# Adafruit_LIS3MDL_LSM6DSOX.net
KiCad netlist of a schematic drawn in EAGLE
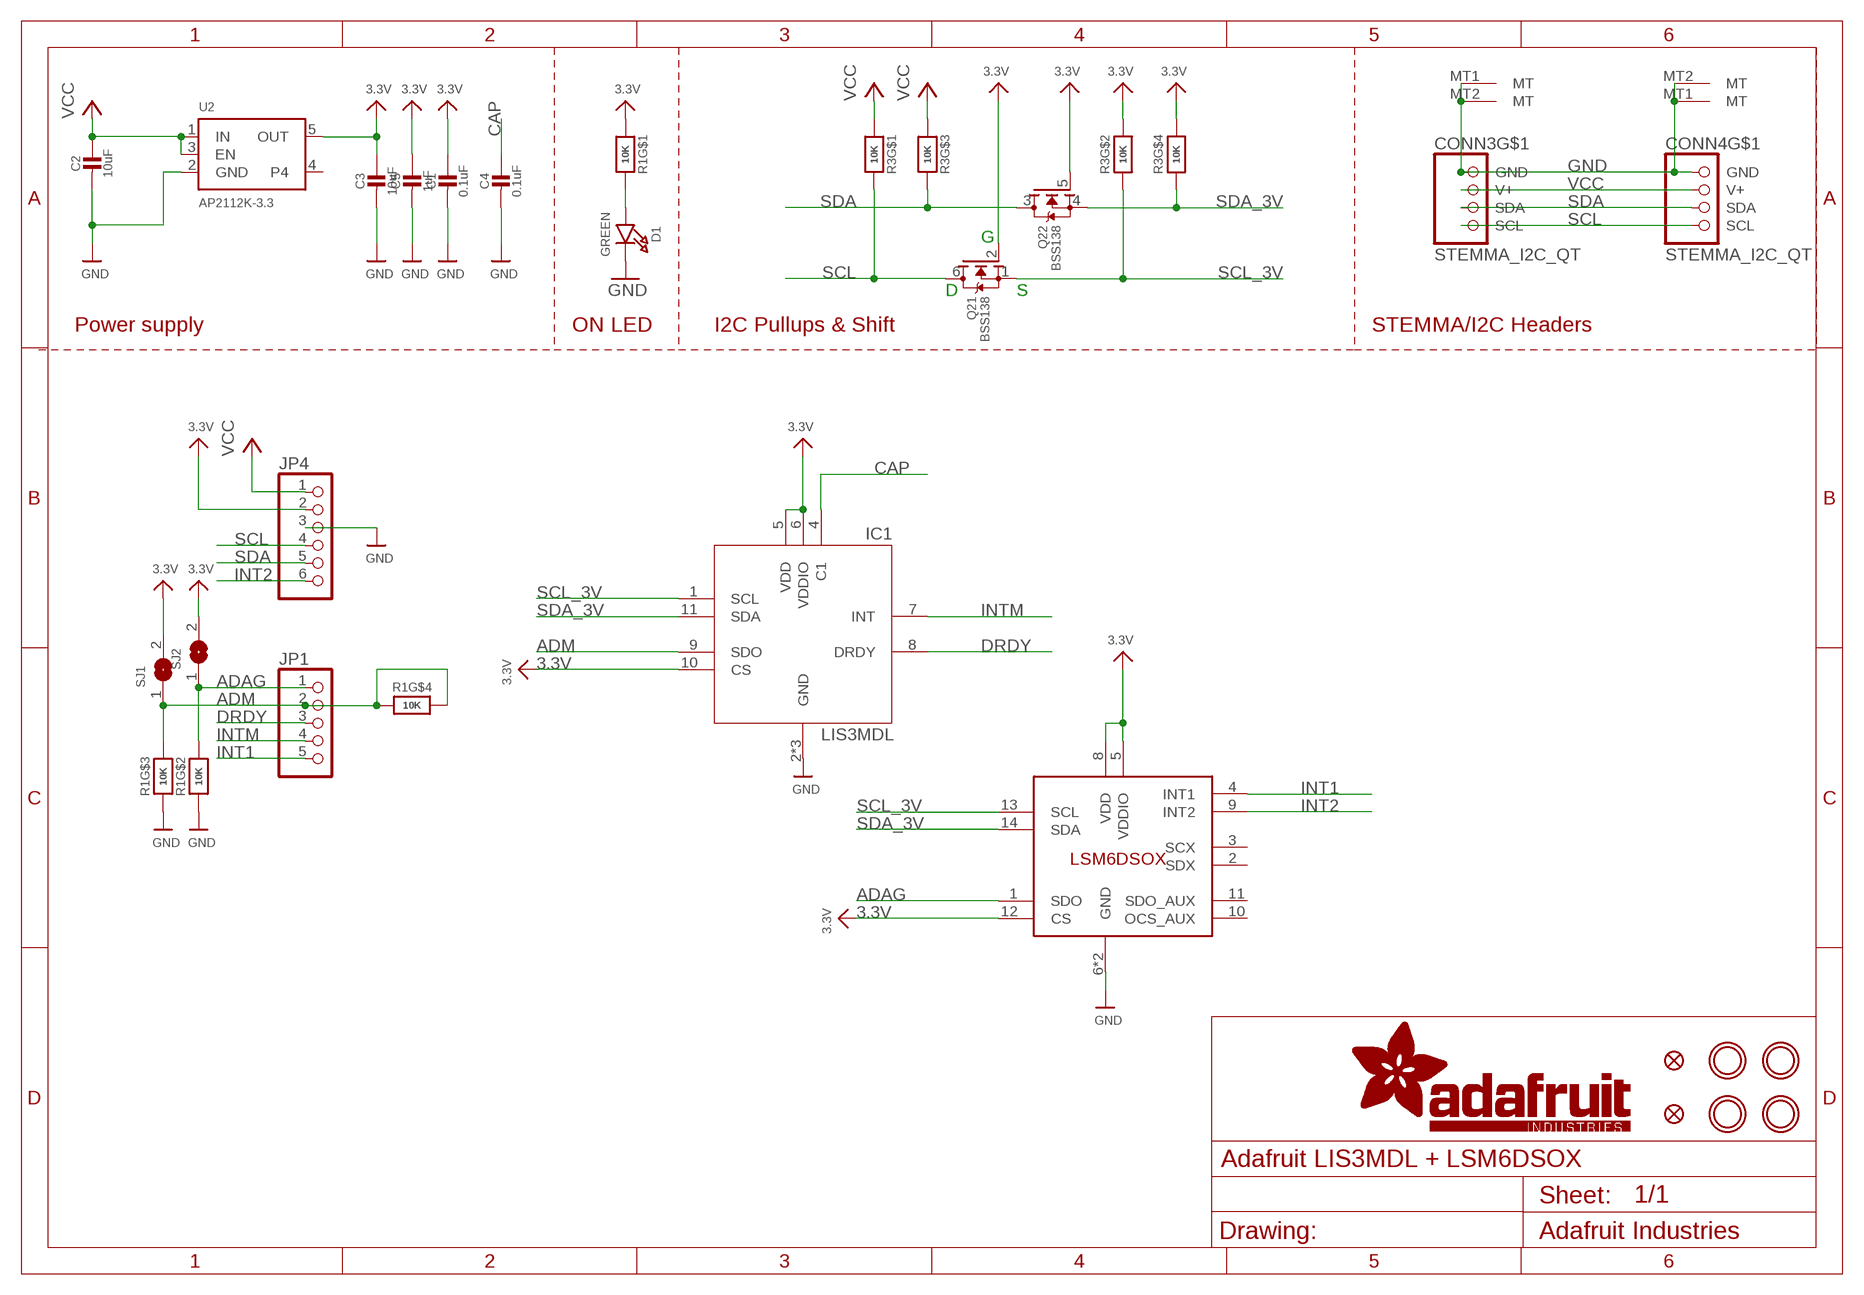
[diagram p0: schematic, sheet 1]

(export (version "E")
  (design (tool "Eeschema 10.0.6"))
  (components
    (comp (ref "C1")
      (value "0.1uF")
      (footprint "eagle-import:0603-NO")
      (libsource (lib "eagle-import") (part "CAP_CERAMIC0603_NO"))
    )
    (comp (ref "C2")
      (value "10uF")
      (footprint "eagle-import:0805-NO")
      (libsource (lib "eagle-import") (part "CAP_CERAMIC0805-NOOUTLINE"))
    )
    (comp (ref "C3")
      (value "10uF")
      (footprint "eagle-import:0805-NO")
      (libsource (lib "eagle-import") (part "CAP_CERAMIC0805-NOOUTLINE"))
    )
    (comp (ref "C4")
      (value "0.1uF")
      (footprint "eagle-import:0603-NO")
      (libsource (lib "eagle-import") (part "CAP_CERAMIC0603_NO"))
    )
    (comp (ref "C5")
      (value "1uF")
      (footprint "eagle-import:0603-NO")
      (libsource (lib "eagle-import") (part "CAP_CERAMIC0603_NO"))
    )
    (comp (ref "CONN3")
      (value "STEMMA_I2C_QT")
      (footprint "eagle-import:JST_SH4")
      (libsource (lib "eagle-import") (part "STEMMA_I2C_QT"))
    )
    (comp (ref "CONN4")
      (value "STEMMA_I2C_QT")
      (footprint "eagle-import:JST_SH4")
      (libsource (lib "eagle-import") (part "STEMMA_I2C_QT"))
    )
    (comp (ref "D1")
      (value "GREEN")
      (footprint "eagle-import:CHIPLED_0603_NOOUTLINE")
      (libsource (lib "eagle-import") (part "LED0603_NOOUTLINE"))
    )
    (comp (ref "FID3")
      (value "FIDUCIAL_1MM")
      (footprint "eagle-import:FIDUCIAL_1MM")
      (libsource (lib "eagle-import") (part "FIDUCIAL_1MM"))
    )
    (comp (ref "FID4")
      (value "FIDUCIAL_1MM")
      (footprint "eagle-import:FIDUCIAL_1MM")
      (libsource (lib "eagle-import") (part "FIDUCIAL_1MM"))
    )
    (comp (ref "IC1")
      (value "LIS3MDL")
      (footprint "eagle-import:LGA12_2X2MM")
      (libsource (lib "eagle-import") (part "LIS3MDL"))
    )
    (comp (ref "JP1")
      (value "HEADER-1X570MIL")
      (footprint "eagle-import:1X05_ROUND_70")
      (libsource (lib "eagle-import") (part "HEADER-1X570MIL"))
    )
    (comp (ref "JP4")
      (value "HEADER-1X670MIL")
      (footprint "eagle-import:1X06_ROUND_70")
      (libsource (lib "eagle-import") (part "HEADER-1X670MIL"))
    )
    (comp (ref "Q2")
      (value "BSS138")
      (footprint "eagle-import:SOT363")
      (libsource (lib "eagle-import") (part "MOSFET-N_DUAL"))
    )
    (comp (ref "R1")
      (value "10K")
      (footprint "eagle-import:RESPACK_4X0603")
      (libsource (lib "eagle-import") (part "RESISTOR_4PACK"))
    )
    (comp (ref "R3")
      (value "10K")
      (footprint "eagle-import:RESPACK_4X0603")
      (libsource (lib "eagle-import") (part "RESISTOR_4PACK"))
    )
    (comp (ref "SJ1")
      (value "SOLDERJUMPER")
      (footprint "eagle-import:SOLDERJUMPER_ARROW_NOPASTE")
      (libsource (lib "eagle-import") (part "SOLDERJUMPER"))
    )
    (comp (ref "SJ2")
      (value "SOLDERJUMPER")
      (footprint "eagle-import:SOLDERJUMPER_ARROW_NOPASTE")
      (libsource (lib "eagle-import") (part "SOLDERJUMPER"))
    )
    (comp (ref "U$1")
      (value "MOUNTINGHOLE2.5")
      (footprint "eagle-import:MOUNTINGHOLE_2.5_PLATED")
      (libsource (lib "eagle-import") (part "MOUNTINGHOLE2.5"))
    )
    (comp (ref "U$17")
      (value "MOUNTINGHOLE2.5")
      (footprint "eagle-import:MOUNTINGHOLE_2.5_PLATED")
      (libsource (lib "eagle-import") (part "MOUNTINGHOLE2.5"))
    )
    (comp (ref "U$19")
      (value "MOUNTINGHOLE2.5")
      (footprint "eagle-import:MOUNTINGHOLE_2.5_PLATED")
      (libsource (lib "eagle-import") (part "MOUNTINGHOLE2.5"))
    )
    (comp (ref "U$21")
      (value "MOUNTINGHOLE2.5")
      (footprint "eagle-import:MOUNTINGHOLE_2.5_PLATED")
      (libsource (lib "eagle-import") (part "MOUNTINGHOLE2.5"))
    )
    (comp (ref "U$35")
      (value "LSM6DSOX")
      (footprint "eagle-import:LGA-14L")
      (libsource (lib "eagle-import") (part "LSM6DSOX"))
    )
    (comp (ref "U2")
      (value "AP2112K-3.3")
      (footprint "eagle-import:SOT23-5")
      (libsource (lib "eagle-import") (part "VREG_SOT23-5"))
    )
  )
  (nets
    (net (code "1") (name "/ADAG") (class "Default")
      (node (ref "JP1") (pin "1") (pinfunction "1_1") (pintype "passive"))
      (node (ref "R1") (pin "7") (pinfunction "2_7") (pintype "passive"))
      (node (ref "SJ2") (pin "1") (pinfunction "1_1") (pintype "passive"))
      (node (ref "U$35") (pin "1") (pinfunction "SDO_1") (pintype "bidirectional"))
    )
    (net (code "2") (name "/ADM") (class "Default")
      (node (ref "IC1") (pin "9") (pinfunction "SDO_9") (pintype "bidirectional"))
      (node (ref "JP1") (pin "2") (pinfunction "2_2") (pintype "passive"))
      (node (ref "R1") (pin "4") (pinfunction "1_4") (pintype "passive"))
      (node (ref "R1") (pin "5") (pinfunction "2_5") (pintype "passive"))
      (node (ref "R1") (pin "6") (pinfunction "2_6") (pintype "passive"))
      (node (ref "SJ1") (pin "1") (pinfunction "1_1") (pintype "passive"))
    )
    (net (code "3") (name "/CAP") (class "Default")
      (node (ref "C4") (pin "1") (pinfunction "1_1") (pintype "passive"))
      (node (ref "IC1") (pin "4") (pinfunction "C1_4") (pintype "input"))
    )
    (net (code "4") (name "/DRDY") (class "Default")
      (node (ref "IC1") (pin "8") (pinfunction "DRDY_8") (pintype "output"))
      (node (ref "JP1") (pin "3") (pinfunction "3_3") (pintype "passive"))
    )
    (net (code "5") (name "/INT1") (class "Default")
      (node (ref "JP1") (pin "5") (pinfunction "5_5") (pintype "passive"))
      (node (ref "U$35") (pin "4") (pinfunction "INT1_4") (pintype "bidirectional"))
    )
    (net (code "6") (name "/INT2") (class "Default")
      (node (ref "JP4") (pin "6") (pinfunction "6_6") (pintype "passive"))
      (node (ref "U$35") (pin "9") (pinfunction "INT2_9") (pintype "bidirectional"))
    )
    (net (code "7") (name "/INTM") (class "Default")
      (node (ref "IC1") (pin "7") (pinfunction "INT_7") (pintype "output"))
      (node (ref "JP1") (pin "4") (pinfunction "4_4") (pintype "passive"))
    )
    (net (code "8") (name "/SCL") (class "Default")
      (node (ref "CONN3") (pin "4") (pinfunction "SCL_4") (pintype "passive"))
      (node (ref "CONN4") (pin "4") (pinfunction "SCL_4") (pintype "passive"))
      (node (ref "JP4") (pin "4") (pinfunction "4_4") (pintype "passive"))
      (node (ref "Q2") (pin "6") (pinfunction "D_6") (pintype "bidirectional"))
      (node (ref "R3") (pin "8") (pinfunction "2_8") (pintype "passive"))
    )
    (net (code "9") (name "/SCL_3V") (class "Default")
      (node (ref "IC1") (pin "1") (pinfunction "SCL_1") (pintype "input"))
      (node (ref "Q2") (pin "1") (pinfunction "S_1") (pintype "bidirectional"))
      (node (ref "R3") (pin "7") (pinfunction "2_7") (pintype "passive"))
      (node (ref "U$35") (pin "13") (pinfunction "SCL_13") (pintype "bidirectional"))
    )
    (net (code "10") (name "/SDA") (class "Default")
      (node (ref "CONN3") (pin "3") (pinfunction "SDA_3") (pintype "passive"))
      (node (ref "CONN4") (pin "3") (pinfunction "SDA_3") (pintype "passive"))
      (node (ref "JP4") (pin "5") (pinfunction "5_5") (pintype "passive"))
      (node (ref "Q2") (pin "3") (pinfunction "D_3") (pintype "bidirectional"))
      (node (ref "R3") (pin "6") (pinfunction "2_6") (pintype "passive"))
    )
    (net (code "11") (name "/SDA_3V") (class "Default")
      (node (ref "IC1") (pin "11") (pinfunction "SDA_11") (pintype "bidirectional"))
      (node (ref "Q2") (pin "4") (pinfunction "S_4") (pintype "bidirectional"))
      (node (ref "R3") (pin "5") (pinfunction "2_5") (pintype "passive"))
      (node (ref "U$35") (pin "14") (pinfunction "SDA_14") (pintype "bidirectional"))
    )
    (net (code "12") (name "3.3V") (class "Default")
      (node (ref "C1") (pin "1") (pinfunction "1_1") (pintype "passive"))
      (node (ref "C3") (pin "1") (pinfunction "1_1") (pintype "passive"))
      (node (ref "C5") (pin "1") (pinfunction "1_1") (pintype "passive"))
      (node (ref "IC1") (pin "10") (pinfunction "CS_10") (pintype "input"))
      (node (ref "IC1") (pin "5") (pinfunction "VDD_5") (pintype "power_in"))
      (node (ref "IC1") (pin "6") (pinfunction "VDDIO_6") (pintype "power_in"))
      (node (ref "JP4") (pin "2") (pinfunction "2_2") (pintype "passive"))
      (node (ref "Q2") (pin "2") (pinfunction "G_2") (pintype "bidirectional"))
      (node (ref "Q2") (pin "5") (pinfunction "G_5") (pintype "bidirectional"))
      (node (ref "R1") (pin "1") (pinfunction "1_1") (pintype "passive"))
      (node (ref "R3") (pin "2") (pinfunction "1_2") (pintype "passive"))
      (node (ref "R3") (pin "4") (pinfunction "1_4") (pintype "passive"))
      (node (ref "SJ1") (pin "2") (pinfunction "2_2") (pintype "passive"))
      (node (ref "SJ2") (pin "2") (pinfunction "2_2") (pintype "passive"))
      (node (ref "U$35") (pin "12") (pinfunction "CS_12") (pintype "bidirectional"))
      (node (ref "U$35") (pin "5") (pinfunction "VDDIO_5") (pintype "power_in"))
      (node (ref "U$35") (pin "8") (pinfunction "VDD_8") (pintype "power_in"))
      (node (ref "U2") (pin "5") (pinfunction "OUT_5") (pintype "power_in"))
    )
    (net (code "13") (name "GND") (class "Default")
      (node (ref "C1") (pin "2") (pinfunction "2_2") (pintype "passive"))
      (node (ref "C2") (pin "2") (pinfunction "2_2") (pintype "passive"))
      (node (ref "C3") (pin "2") (pinfunction "2_2") (pintype "passive"))
      (node (ref "C4") (pin "2") (pinfunction "2_2") (pintype "passive"))
      (node (ref "C5") (pin "2") (pinfunction "2_2") (pintype "passive"))
      (node (ref "CONN3") (pin "1") (pinfunction "GND_1") (pintype "passive"))
      (node (ref "CONN3") (pin "MT1") (pinfunction "MT_MT1") (pintype "bidirectional"))
      (node (ref "CONN3") (pin "MT2") (pinfunction "MT_MT2") (pintype "bidirectional"))
      (node (ref "CONN4") (pin "1") (pinfunction "GND_1") (pintype "passive"))
      (node (ref "CONN4") (pin "MT1") (pinfunction "MT_MT1") (pintype "bidirectional"))
      (node (ref "CONN4") (pin "MT2") (pinfunction "MT_MT2") (pintype "bidirectional"))
      (node (ref "D1") (pin "C") (pinfunction "C_C") (pintype "passive"))
      (node (ref "IC1") (pin "12") (pinfunction "GND_12") (pintype "power_in"))
      (node (ref "IC1") (pin "2") (pinfunction "GND_2") (pintype "power_in"))
      (node (ref "IC1") (pin "3") (pinfunction "GND_3") (pintype "power_in"))
      (node (ref "JP4") (pin "3") (pinfunction "3_3") (pintype "passive"))
      (node (ref "R1") (pin "2") (pinfunction "1_2") (pintype "passive"))
      (node (ref "R1") (pin "3") (pinfunction "1_3") (pintype "passive"))
      (node (ref "U$35") (pin "6") (pinfunction "GND_6") (pintype "power_in"))
      (node (ref "U$35") (pin "7") (pinfunction "GND_7") (pintype "power_in"))
      (node (ref "U2") (pin "2") (pinfunction "GND_2") (pintype "power_in"))
    )
    (net (code "14") (name "Net-(R1A-2)") (class "Default")
      (node (ref "D1") (pin "A") (pinfunction "A_A") (pintype "passive"))
      (node (ref "R1") (pin "8") (pinfunction "2_8") (pintype "passive"))
    )
    (net (code "15") (name "VCC") (class "Default")
      (node (ref "C2") (pin "1") (pinfunction "1_1") (pintype "passive"))
      (node (ref "CONN3") (pin "2") (pinfunction "V+_2") (pintype "passive"))
      (node (ref "CONN4") (pin "2") (pinfunction "V+_2") (pintype "passive"))
      (node (ref "JP4") (pin "1") (pinfunction "1_1") (pintype "passive"))
      (node (ref "R3") (pin "1") (pinfunction "1_1") (pintype "passive"))
      (node (ref "R3") (pin "3") (pinfunction "1_3") (pintype "passive"))
      (node (ref "U2") (pin "1") (pinfunction "IN_1") (pintype "power_in"))
      (node (ref "U2") (pin "3") (pinfunction "EN_3") (pintype "input"))
    )
    (net (code "16") (name "unconnected-(U$35-OCS_AUX-Pad10)") (class "Default")
      (node (ref "U$35") (pin "10") (pinfunction "OCS_AUX_10") (pintype "bidirectional"))
    )
    (net (code "17") (name "unconnected-(U$35-SCX-Pad3)") (class "Default")
      (node (ref "U$35") (pin "3") (pinfunction "SCX_3") (pintype "bidirectional"))
    )
    (net (code "18") (name "unconnected-(U$35-SDO_AUX-Pad11)") (class "Default")
      (node (ref "U$35") (pin "11") (pinfunction "SDO_AUX_11") (pintype "bidirectional"))
    )
    (net (code "19") (name "unconnected-(U$35-SDX-Pad2)") (class "Default")
      (node (ref "U$35") (pin "2") (pinfunction "SDX_2") (pintype "bidirectional"))
    )
    (net (code "20") (name "unconnected-(U2-P4-Pad4)") (class "Default")
      (node (ref "U2") (pin "4") (pinfunction "P4_4") (pintype "bidirectional"))
    )
  )
)
